# ESP32-S3_Devkit_Replica.net
KiCad netlist of a schematic drawn in Altium Designer
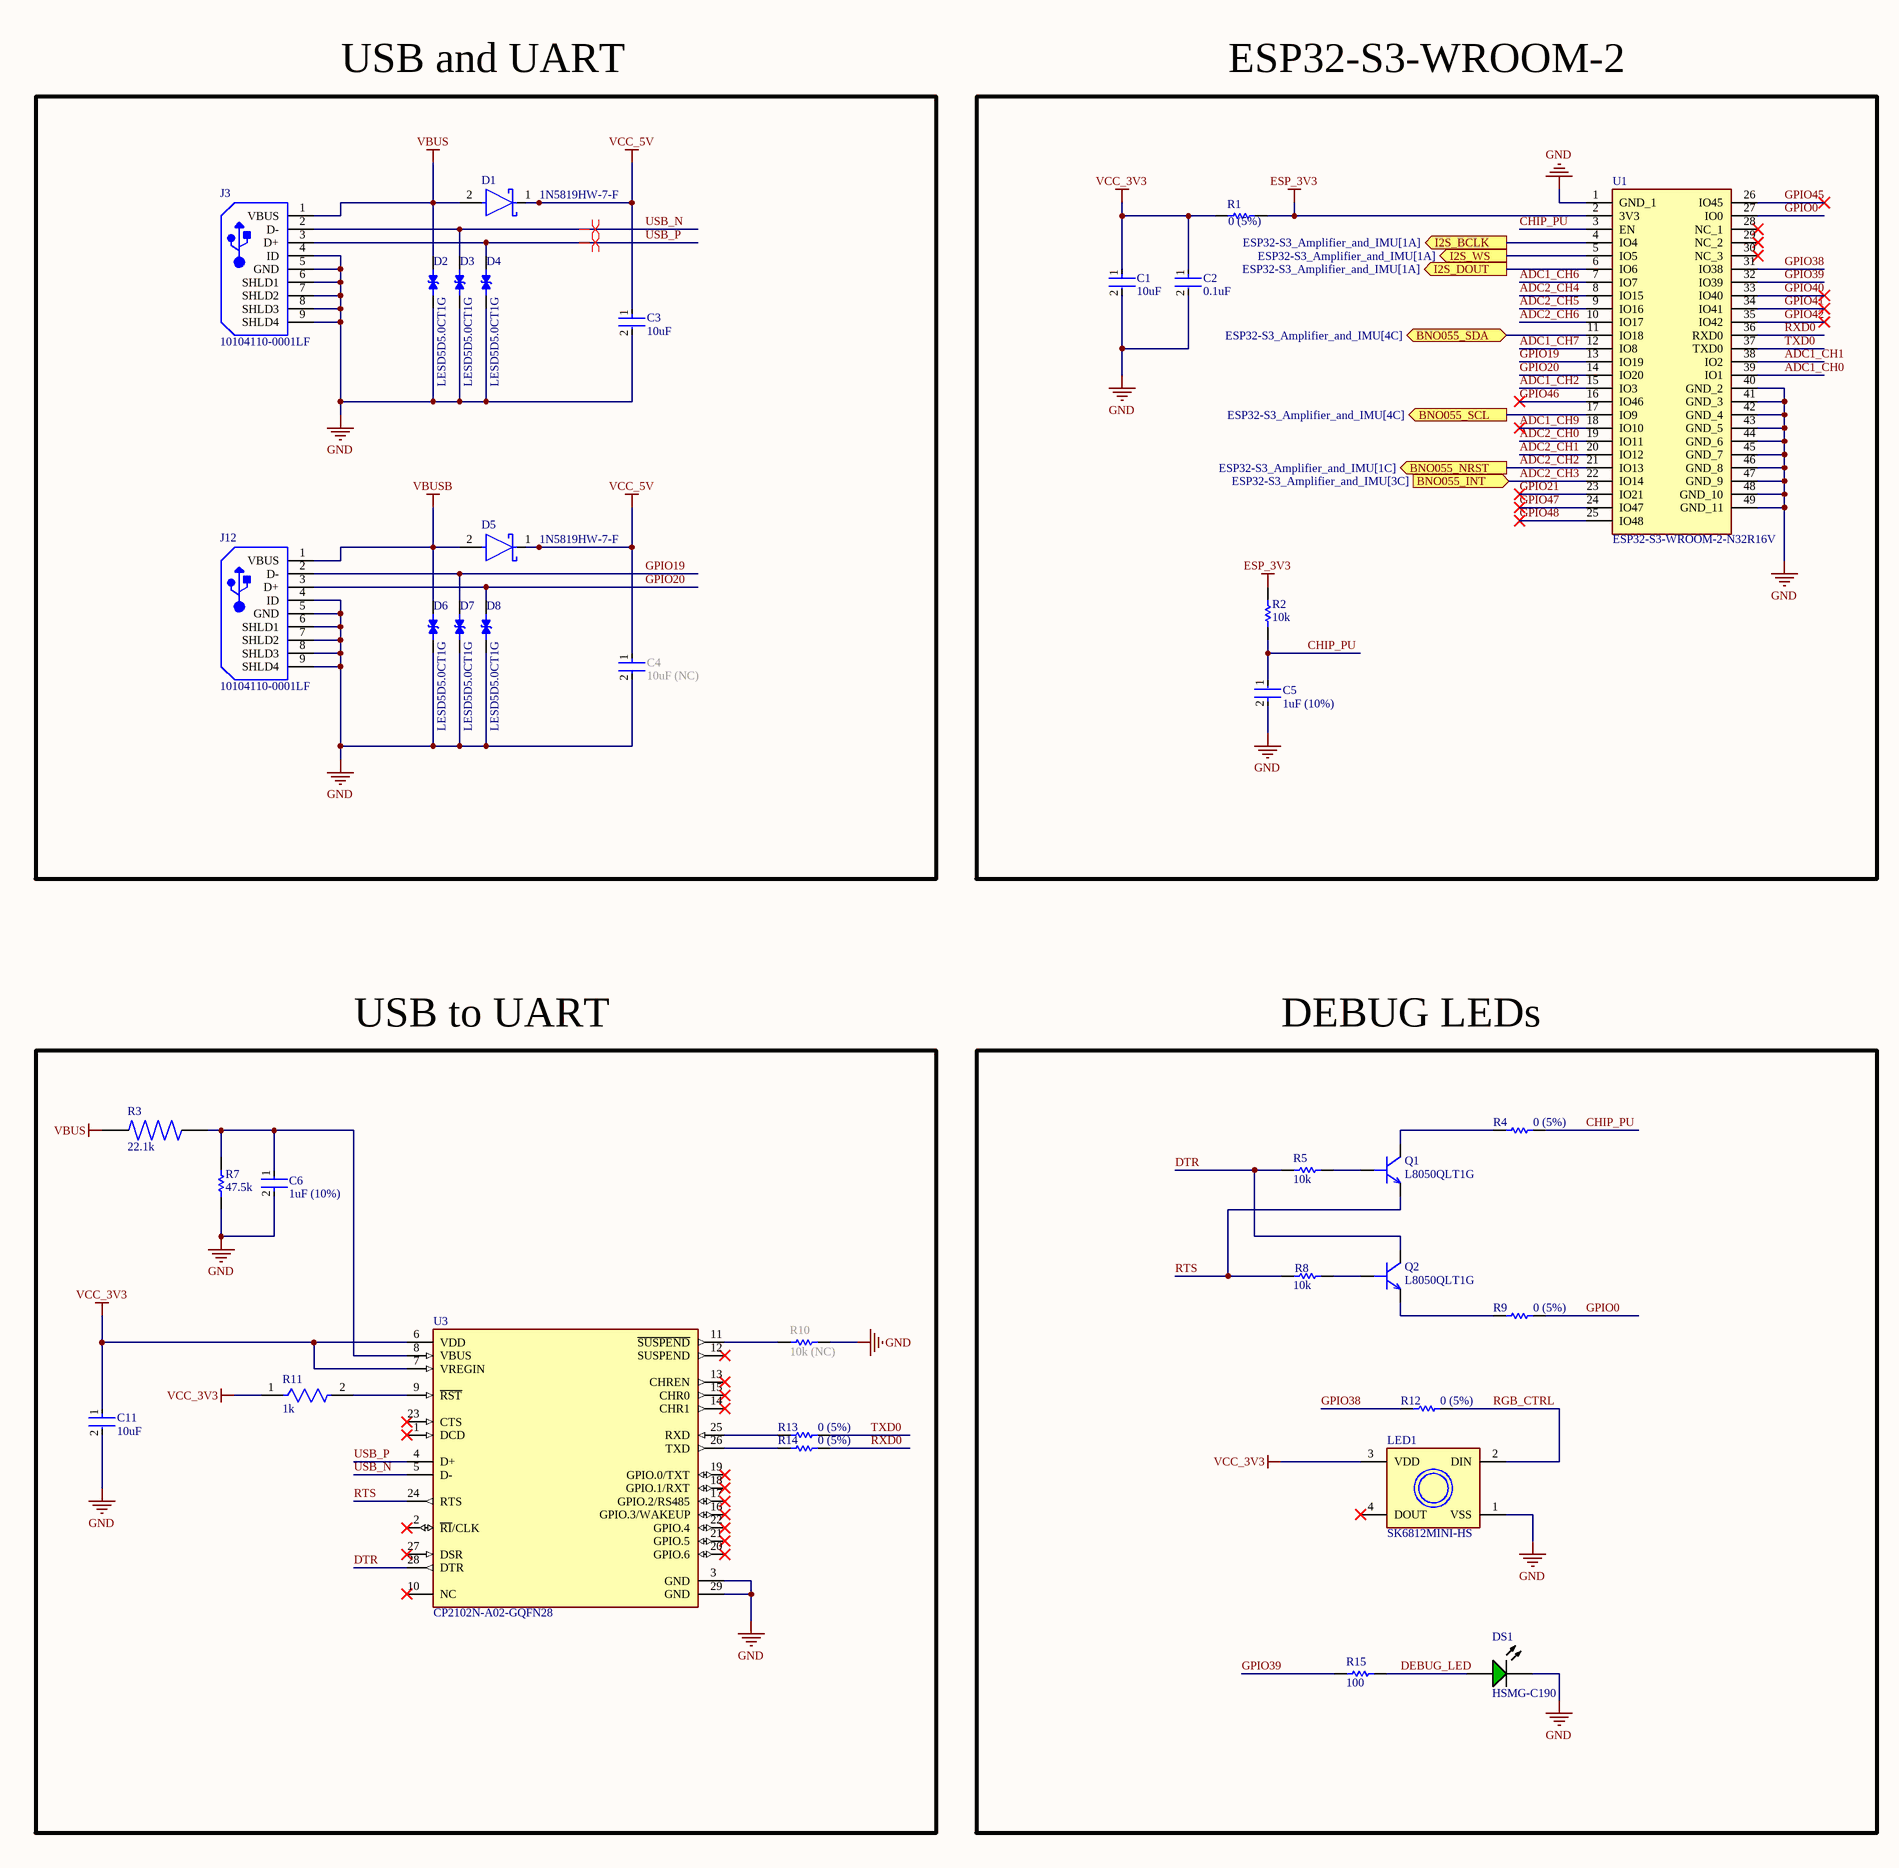
[diagram p0: ESP32-S3_Devkit_Replica.SchDoc, left]
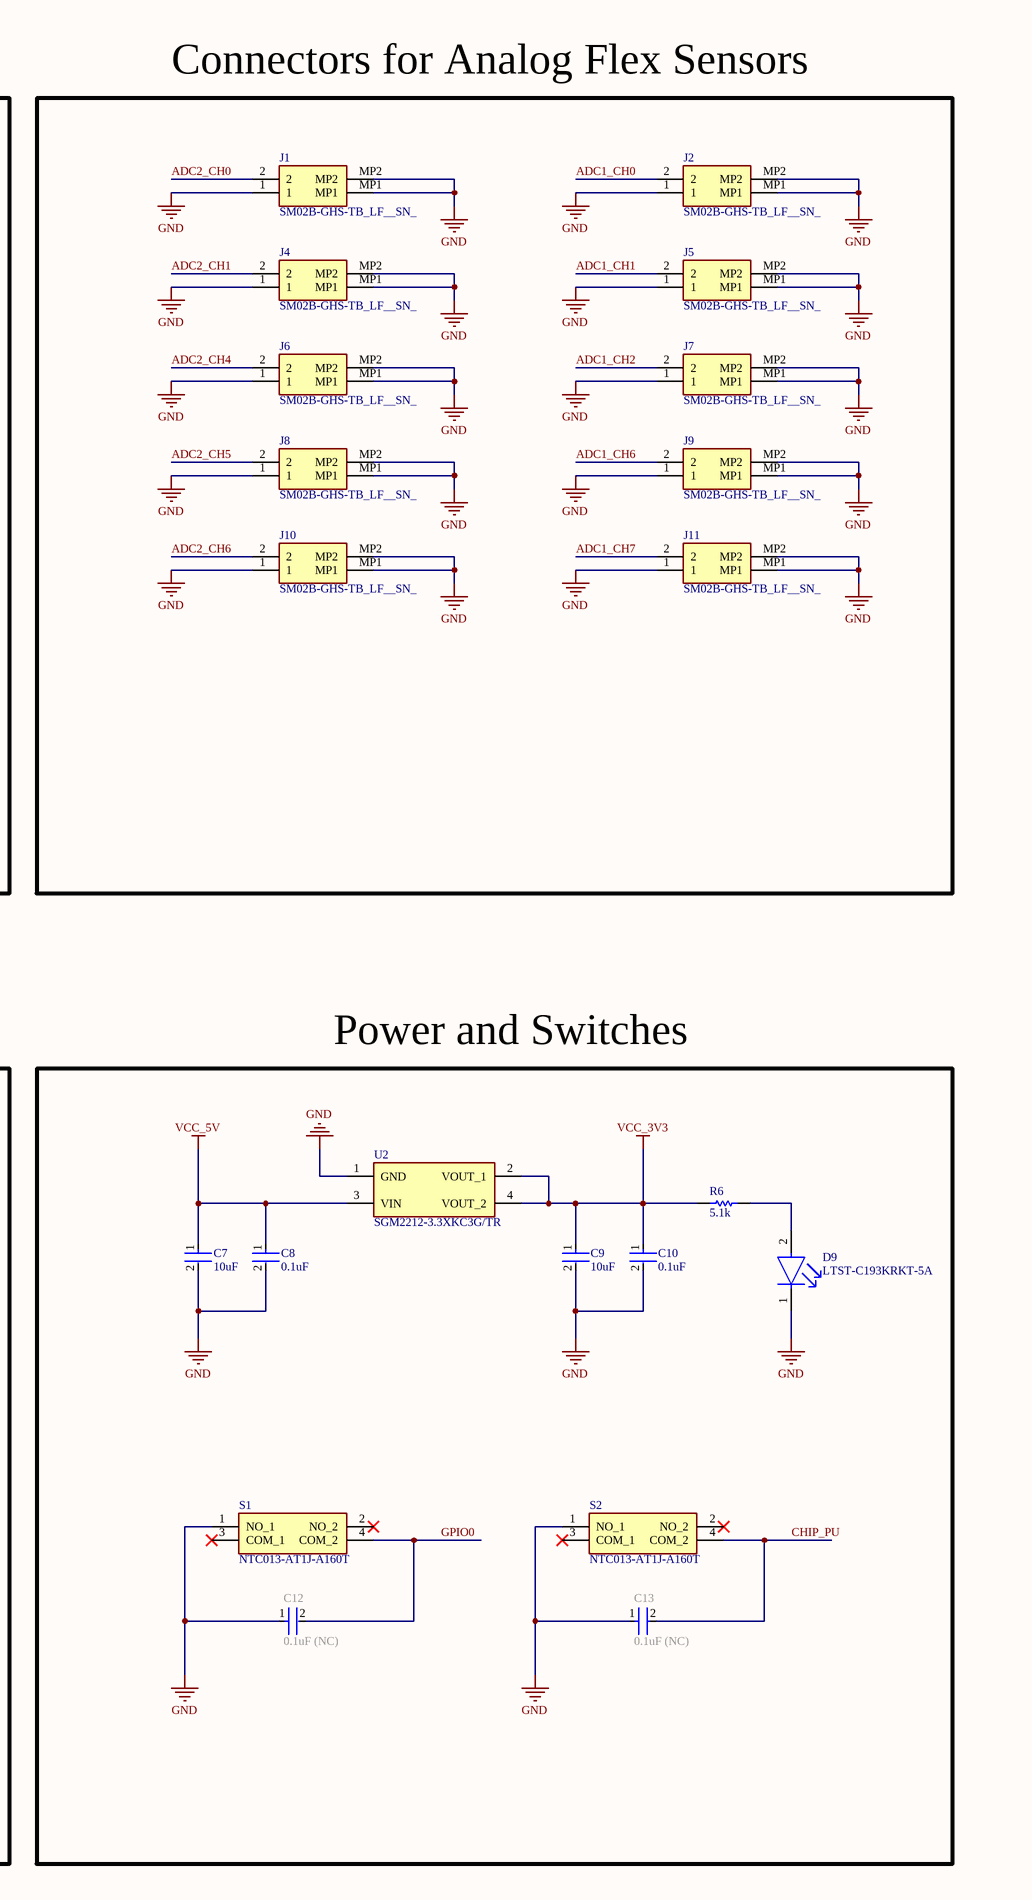
[diagram p1: ESP32-S3_Devkit_Replica.SchDoc, right]

(export (version "E")
  (design (tool "Eeschema 10.0.6"))
  (components
    (comp (ref "C1")
      (value "GRM21BC8YA106KE11L")
      (footprint "FP-GRM21B-0_2-e0_2_0_7-IPC_B")
      (description "Chip Multilayer Ceramic Capacitors for General Purpose, 0805, 10uF, X6S, 22%, 10%, 35V")
      (fields (field (name "CAPACITANCE") "10uF") (field (name "TOLERANCE") "10%"))
      (libsource (lib "Altium Content Vault") (part "b4654b650e69147ec39a6b967a45e02"))
    )
    (comp (ref "C2")
      (value "C1005X7R1H104K050BB")
      (footprint "FP-C1005-050-0_05-IPC_C")
      (description "Multilayer Ceramic Capacitors 100nF ±10% 50V X7R SMD 0402")
      (fields
        (field (name "VOLTAGE") "50V")
        (field (name "CAPACITANCE") "0.1uF")
        (field (name "TOLERANCE") "10%")
      )
      (libsource (lib "Altium Content Vault") (part "b4654b650e69147ec39a6b967a45e02"))
    )
    (comp (ref "C3")
      (value "GRM21BC8YA106KE11L")
      (footprint "FP-GRM21B-0_2-e0_2_0_7-IPC_B")
      (description "Chip Multilayer Ceramic Capacitors for General Purpose, 0805, 10uF, X6S, 22%, 10%, 35V")
      (fields (field (name "CAPACITANCE") "10uF") (field (name "TOLERANCE") "10%"))
      (libsource (lib "Altium Content Vault") (part "b4654b650e69147ec39a6b967a45e02"))
    )
    (comp (ref "C4")
      (value "GRM21BC8YA106KE11L")
      (footprint "FP-GRM21B-0_2-e0_2_0_7-IPC_B")
      (description "Chip Multilayer Ceramic Capacitors for General Purpose, 0805, 10uF, X6S, 22%, 10%, 35V")
      (fields (field (name "CAPACITANCE") "10uF (NC)") (field (name "TOLERANCE") "10%"))
      (libsource (lib "Altium Content Vault") (part "b4654b650e69147ec39a6b967a45e02"))
    )
    (comp (ref "C5")
      (value "C1608X5R1H105K080AB")
      (footprint "FP-C1608-080-0_1-IPC_B")
      (description "Multilayer Ceramic Capacitors 1μF ±10% 50V X5R SMD 0603")
      (fields
        (field (name "VOLTAGE") "50V")
        (field (name "CAPACITANCE") "1uF (10%)")
        (field (name "TOLERANCE") "10%")
      )
      (libsource (lib "Altium Content Vault") (part "236180d848d6139a670b325ea6854c9"))
    )
    (comp (ref "C6")
      (value "C1608X5R1H105K080AB")
      (footprint "FP-C1608-080-0_1-IPC_B")
      (description "Multilayer Ceramic Capacitors 1μF ±10% 50V X5R SMD 0603")
      (fields
        (field (name "VOLTAGE") "50V")
        (field (name "CAPACITANCE") "1uF (10%)")
        (field (name "TOLERANCE") "10%")
      )
      (libsource (lib "Altium Content Vault") (part "236180d848d6139a670b325ea6854c9"))
    )
    (comp (ref "C7")
      (value "GRM21BC8YA106KE11L")
      (footprint "FP-GRM21B-0_2-e0_2_0_7-IPC_B")
      (description "Chip Multilayer Ceramic Capacitors for General Purpose, 0805, 10uF, X6S, 22%, 10%, 35V")
      (fields (field (name "CAPACITANCE") "10uF") (field (name "TOLERANCE") "10%"))
      (libsource (lib "Altium Content Vault") (part "b4654b650e69147ec39a6b967a45e02"))
    )
    (comp (ref "C8")
      (value "C1005X7R1H104K050BB")
      (footprint "FP-C1005-050-0_05-IPC_C")
      (description "Multilayer Ceramic Capacitors 100nF ±10% 50V X7R SMD 0402")
      (fields
        (field (name "VOLTAGE") "50V")
        (field (name "CAPACITANCE") "0.1uF")
        (field (name "TOLERANCE") "10%")
      )
      (libsource (lib "Altium Content Vault") (part "b4654b650e69147ec39a6b967a45e02"))
    )
    (comp (ref "C9")
      (value "GRM21BC8YA106KE11L")
      (footprint "FP-GRM21B-0_2-e0_2_0_7-IPC_B")
      (description "Chip Multilayer Ceramic Capacitors for General Purpose, 0805, 10uF, X6S, 22%, 10%, 35V")
      (fields (field (name "CAPACITANCE") "10uF") (field (name "TOLERANCE") "10%"))
      (libsource (lib "Altium Content Vault") (part "b4654b650e69147ec39a6b967a45e02"))
    )
    (comp (ref "C10")
      (value "C1005X7R1H104K050BB")
      (footprint "FP-C1005-050-0_05-IPC_C")
      (description "Multilayer Ceramic Capacitors 100nF ±10% 50V X7R SMD 0402")
      (fields
        (field (name "VOLTAGE") "50V")
        (field (name "CAPACITANCE") "0.1uF")
        (field (name "TOLERANCE") "10%")
      )
      (libsource (lib "Altium Content Vault") (part "b4654b650e69147ec39a6b967a45e02"))
    )
    (comp (ref "C11")
      (value "GRM21BC8YA106KE11L")
      (footprint "FP-GRM21B-0_2-e0_2_0_7-IPC_B")
      (description "Chip Multilayer Ceramic Capacitors for General Purpose, 0805, 10uF, X6S, 22%, 10%, 35V")
      (fields (field (name "CAPACITANCE") "10uF") (field (name "TOLERANCE") "10%"))
      (libsource (lib "Altium Content Vault") (part "b4654b650e69147ec39a6b967a45e02"))
    )
    (comp (ref "C12")
      (value "C1005X7R1H104K050BB")
      (footprint "FP-C1005-050-0_05-IPC_C")
      (description "Multilayer Ceramic Capacitors 100nF ±10% 50V X7R SMD 0402")
      (fields
        (field (name "VOLTAGE") "50V")
        (field (name "CAPACITANCE") "0.1uF (NC)")
        (field (name "TOLERANCE") "10%")
      )
      (libsource (lib "Altium Content Vault") (part "b4654b650e69147ec39a6b967a45e02"))
    )
    (comp (ref "C13")
      (value "C1005X7R1H104K050BB")
      (footprint "FP-C1005-050-0_05-IPC_C")
      (description "Multilayer Ceramic Capacitors 100nF ±10% 50V X7R SMD 0402")
      (fields
        (field (name "VOLTAGE") "50V")
        (field (name "CAPACITANCE") "0.1uF (NC)")
        (field (name "TOLERANCE") "10%")
      )
      (libsource (lib "Altium Content Vault") (part "b4654b650e69147ec39a6b967a45e02"))
    )
    (comp (ref "D1")
      (value "1N5819HW-7-F")
      (footprint "FP-SOD123-IPC_A")
      (description "DIODE SCHOTTKY 40V 1A SOD123")
      (libsource (lib "Altium Content Vault") (part "1d6ec82d83fb6aee721767c19dac4b9"))
    )
    (comp (ref "D2")
      (value "LESD5D5.0CT1G")
      (footprint "TVS_LESD5D5.0CT1G")
      (description "Transient Voltage Suppressors for ESD Protection")
      (fields (field (name "MF") "Leshan Radio Co."))
      (libsource (lib "GesturaGloveComponents") (part "LESD5D5.0CT1G"))
    )
    (comp (ref "D3")
      (value "LESD5D5.0CT1G")
      (footprint "TVS_LESD5D5.0CT1G")
      (description "Transient Voltage Suppressors for ESD Protection")
      (fields (field (name "MF") "Leshan Radio Co."))
      (libsource (lib "GesturaGloveComponents") (part "LESD5D5.0CT1G"))
    )
    (comp (ref "D4")
      (value "LESD5D5.0CT1G")
      (footprint "TVS_LESD5D5.0CT1G")
      (description "Transient Voltage Suppressors for ESD Protection")
      (fields (field (name "MF") "Leshan Radio Co."))
      (libsource (lib "GesturaGloveComponents") (part "LESD5D5.0CT1G"))
    )
    (comp (ref "D5")
      (value "1N5819HW-7-F")
      (footprint "FP-SOD123-IPC_A")
      (description "DIODE SCHOTTKY 40V 1A SOD123")
      (libsource (lib "Altium Content Vault") (part "1d6ec82d83fb6aee721767c19dac4b9"))
    )
    (comp (ref "D6")
      (value "LESD5D5.0CT1G")
      (footprint "TVS_LESD5D5.0CT1G")
      (description "Transient Voltage Suppressors for ESD Protection")
      (fields (field (name "MF") "Leshan Radio Co."))
      (libsource (lib "GesturaGloveComponents") (part "LESD5D5.0CT1G"))
    )
    (comp (ref "D7")
      (value "LESD5D5.0CT1G")
      (footprint "TVS_LESD5D5.0CT1G")
      (description "Transient Voltage Suppressors for ESD Protection")
      (fields (field (name "MF") "Leshan Radio Co."))
      (libsource (lib "GesturaGloveComponents") (part "LESD5D5.0CT1G"))
    )
    (comp (ref "D8")
      (value "LESD5D5.0CT1G")
      (footprint "TVS_LESD5D5.0CT1G")
      (description "Transient Voltage Suppressors for ESD Protection")
      (fields (field (name "MF") "Leshan Radio Co."))
      (libsource (lib "GesturaGloveComponents") (part "LESD5D5.0CT1G"))
    )
    (comp (ref "D9")
      (value "LTST-C193KRKT-5A")
      (footprint "FP-LTST-C193KRKT-5A-MFG")
      (description "LED RED CLEAR CHIP SMD")
      (libsource (lib "Altium Content Vault") (part "8706943c75ba83719d021d2fdc84c58"))
    )
    (comp (ref "DS1")
      (value "HSMG-C190")
      (footprint "AVAG-HSMX-C190_V")
      (description "Chip LED, Green, 2.2 V, -40 to 85 degC, 2-Pin SMD, RoHS, Tape and Reel")
      (libsource (lib "Altium Content Vault") (part "LED-GREEN-AK-2"))
    )
    (comp (ref "J1")
      (value "SM02B-GHS-TB_LF__SN_")
      (footprint "GesturaGloveComponents:SM02BGHSTBLFSN")
      (description "Connector")
      (fields
        (field (name "MANUFACTURER_PART_NUMBER") "SM02B-GHS-TB(LF)(SN);-")
        (field (name "MOUSER PART NUMBER") "306-SM02BGHSTBLFSN")
      )
      (libsource (lib "GesturaGloveComponents") (part "SM02B-GHS-TB_LF__SN_"))
    )
    (comp (ref "J2")
      (value "SM02B-GHS-TB_LF__SN_")
      (footprint "GesturaGloveComponents:SM02BGHSTBLFSN")
      (description "Connector")
      (fields
        (field (name "MANUFACTURER_PART_NUMBER") "SM02B-GHS-TB(LF)(SN);-")
        (field (name "MOUSER PART NUMBER") "306-SM02BGHSTBLFSN")
      )
      (libsource (lib "GesturaGloveComponents") (part "SM02B-GHS-TB_LF__SN_"))
    )
    (comp (ref "J3")
      (value "10104110-0001LF")
      (footprint "FCI-10104110-0001LF_V")
      (description "Micro USB, Receptacle, -55 to 85 degC, 5-Pin SMD, RoHS, Tape and Reel")
      (fields (field (name "MANUFACTURER") "FCI Electronics"))
      (libsource (lib "Altium Content Vault") (part "USB-5-4SHLD"))
    )
    (comp (ref "J4")
      (value "SM02B-GHS-TB_LF__SN_")
      (footprint "GesturaGloveComponents:SM02BGHSTBLFSN")
      (description "Connector")
      (fields
        (field (name "MANUFACTURER_PART_NUMBER") "SM02B-GHS-TB(LF)(SN);-")
        (field (name "MOUSER PART NUMBER") "306-SM02BGHSTBLFSN")
      )
      (libsource (lib "GesturaGloveComponents") (part "SM02B-GHS-TB_LF__SN_"))
    )
    (comp (ref "J5")
      (value "SM02B-GHS-TB_LF__SN_")
      (footprint "GesturaGloveComponents:SM02BGHSTBLFSN")
      (description "Connector")
      (fields
        (field (name "MANUFACTURER_PART_NUMBER") "SM02B-GHS-TB(LF)(SN);-")
        (field (name "MOUSER PART NUMBER") "306-SM02BGHSTBLFSN")
      )
      (libsource (lib "GesturaGloveComponents") (part "SM02B-GHS-TB_LF__SN_"))
    )
    (comp (ref "J6")
      (value "SM02B-GHS-TB_LF__SN_")
      (footprint "GesturaGloveComponents:SM02BGHSTBLFSN")
      (description "Connector")
      (fields
        (field (name "MANUFACTURER_PART_NUMBER") "SM02B-GHS-TB(LF)(SN);-")
        (field (name "MOUSER PART NUMBER") "306-SM02BGHSTBLFSN")
      )
      (libsource (lib "GesturaGloveComponents") (part "SM02B-GHS-TB_LF__SN_"))
    )
    (comp (ref "J7")
      (value "SM02B-GHS-TB_LF__SN_")
      (footprint "GesturaGloveComponents:SM02BGHSTBLFSN")
      (description "Connector")
      (fields
        (field (name "MANUFACTURER_PART_NUMBER") "SM02B-GHS-TB(LF)(SN);-")
        (field (name "MOUSER PART NUMBER") "306-SM02BGHSTBLFSN")
      )
      (libsource (lib "GesturaGloveComponents") (part "SM02B-GHS-TB_LF__SN_"))
    )
    (comp (ref "J8")
      (value "SM02B-GHS-TB_LF__SN_")
      (footprint "GesturaGloveComponents:SM02BGHSTBLFSN")
      (description "Connector")
      (fields
        (field (name "MANUFACTURER_PART_NUMBER") "SM02B-GHS-TB(LF)(SN);-")
        (field (name "MOUSER PART NUMBER") "306-SM02BGHSTBLFSN")
      )
      (libsource (lib "GesturaGloveComponents") (part "SM02B-GHS-TB_LF__SN_"))
    )
    (comp (ref "J9")
      (value "SM02B-GHS-TB_LF__SN_")
      (footprint "GesturaGloveComponents:SM02BGHSTBLFSN")
      (description "Connector")
      (fields
        (field (name "MANUFACTURER_PART_NUMBER") "SM02B-GHS-TB(LF)(SN);-")
        (field (name "MOUSER PART NUMBER") "306-SM02BGHSTBLFSN")
      )
      (libsource (lib "GesturaGloveComponents") (part "SM02B-GHS-TB_LF__SN_"))
    )
    (comp (ref "J10")
      (value "SM02B-GHS-TB_LF__SN_")
      (footprint "GesturaGloveComponents:SM02BGHSTBLFSN")
      (description "Connector")
      (fields
        (field (name "MANUFACTURER_PART_NUMBER") "SM02B-GHS-TB(LF)(SN);-")
        (field (name "MOUSER PART NUMBER") "306-SM02BGHSTBLFSN")
      )
      (libsource (lib "GesturaGloveComponents") (part "SM02B-GHS-TB_LF__SN_"))
    )
    (comp (ref "J11")
      (value "SM02B-GHS-TB_LF__SN_")
      (footprint "GesturaGloveComponents:SM02BGHSTBLFSN")
      (description "Connector")
      (fields
        (field (name "MANUFACTURER_PART_NUMBER") "SM02B-GHS-TB(LF)(SN);-")
        (field (name "MOUSER PART NUMBER") "306-SM02BGHSTBLFSN")
      )
      (libsource (lib "GesturaGloveComponents") (part "SM02B-GHS-TB_LF__SN_"))
    )
    (comp (ref "J12")
      (value "10104110-0001LF")
      (footprint "FCI-10104110-0001LF_V")
      (description "Micro USB, Receptacle, -55 to 85 degC, 5-Pin SMD, RoHS, Tape and Reel")
      (fields (field (name "MANUFACTURER") "FCI Electronics"))
      (libsource (lib "Altium Content Vault") (part "USB-5-4SHLD"))
    )
    (comp (ref "LED1")
      (value "SK6812MINI-HS")
      (footprint "GesturaGloveComponents:SK6812MINI-HS")
      (description "LED")
      (fields (field (name "MANUFACTURER_PART_NUMBER") "ILPH-K501-RGBW-SK6812-05-01"))
      (libsource (lib "GesturaGloveComponents") (part "SK6812MINI-HS"))
    )
    (comp (ref "Q1")
      (value "L8050QLT1G")
      (footprint "L8050QLT1G")
      (description "25V 225mW 800mA NPN SOT-23(SOT-23-3) Bipolar Transistors - BJT ROHS")
      (libsource (lib "GesturaGloveComponents") (part "L8050QLT1G"))
    )
    (comp (ref "Q2")
      (value "L8050QLT1G")
      (footprint "L8050QLT1G")
      (description "25V 225mW 800mA NPN SOT-23(SOT-23-3) Bipolar Transistors - BJT ROHS")
      (libsource (lib "GesturaGloveComponents") (part "L8050QLT1G"))
    )
    (comp (ref "R1")
      (value "ERJ2GE0R00X")
      (footprint "RESC1005X40X25LL05T05")
      (description "Chip Resistor, 0 Ohm, 0.1 W, -55 to 155 degC, 0402 (1005 Metric), RoHS, Tape and Reel")
      (fields
        (field (name "MANUFACTURER") "Panasonic")
        (field (name "RESISTANCE") "0 (5%)")
        (field (name "TOLERANCE") "5%")
      )
      (libsource (lib "Altium Content Vault") (part "RES-2"))
    )
    (comp (ref "R2")
      (value "CRCW040210K0FKEDHP")
      (footprint "RESC1005X40X25ML05T10")
      (description "1")
      (fields (field (name "MANUFACTURER") "Vishay Dale") (field (name "RESISTANCE") "10k"))
      (libsource (lib "Altium Content Vault") (part "RES"))
    )
    (comp (ref "R3")
      (value "22.1k")
      (footprint "GesturaGloveComponents:RES_ERA2AEB2212X")
      (description "Res Thin Film 0402 22.1K Ohm 0.1% 1/16W ±25ppm/°C Molded SMD Punched Paper T/R")
      (fields (field (name "MP") "ERA2AEB2212X"))
      (libsource (lib "GesturaGloveComponents") (part "ERA2AEB2212X"))
    )
    (comp (ref "R4")
      (value "ERJ2GE0R00X")
      (footprint "RESC1005X40X25LL05T05")
      (description "Chip Resistor, 0 Ohm, 0.1 W, -55 to 155 degC, 0402 (1005 Metric), RoHS, Tape and Reel")
      (fields
        (field (name "MANUFACTURER") "Panasonic")
        (field (name "RESISTANCE") "0 (5%)")
        (field (name "TOLERANCE") "5%")
      )
      (libsource (lib "Altium Content Vault") (part "RES-2"))
    )
    (comp (ref "R5")
      (value "CRCW040210K0FKEDHP")
      (footprint "RESC1005X40X25ML05T10")
      (description "1")
      (fields (field (name "MANUFACTURER") "Vishay Dale") (field (name "RESISTANCE") "10k"))
      (libsource (lib "Altium Content Vault") (part "RES"))
    )
    (comp (ref "R6")
      (value "RC0402FR-075K1L")
      (footprint "RESC1005X40X25NL05T10")
      (fields (field (name "MANUFACTURER") "Yageo / Phycomp") (field (name "RESISTANCE") "5.1k"))
      (libsource (lib "Altium Content Vault") (part "RES"))
    )
    (comp (ref "R7")
      (value "CRCW040247K5FKTD")
      (footprint "RESC1005X40X25LL05T05")
      (fields (field (name "MANUFACTURER") "Vishay Dale") (field (name "RESISTANCE") "47.5k"))
      (libsource (lib "Altium Content Vault") (part "RES"))
    )
    (comp (ref "R8")
      (value "CRCW040210K0FKEDHP")
      (footprint "RESC1005X40X25ML05T10")
      (description "1")
      (fields (field (name "MANUFACTURER") "Vishay Dale") (field (name "RESISTANCE") "10k"))
      (libsource (lib "Altium Content Vault") (part "RES"))
    )
    (comp (ref "R9")
      (value "ERJ2GE0R00X")
      (footprint "RESC1005X40X25LL05T05")
      (description "Chip Resistor, 0 Ohm, 0.1 W, -55 to 155 degC, 0402 (1005 Metric), RoHS, Tape and Reel")
      (fields
        (field (name "MANUFACTURER") "Panasonic")
        (field (name "RESISTANCE") "0 (5%)")
        (field (name "TOLERANCE") "5%")
      )
      (libsource (lib "Altium Content Vault") (part "RES-2"))
    )
    (comp (ref "R10")
      (value "CRCW040210K0FKEDHP")
      (footprint "RESC1005X40X25ML05T10")
      (description "1")
      (fields (field (name "MANUFACTURER") "Vishay Dale") (field (name "RESISTANCE") "10k (NC)"))
      (libsource (lib "Altium Content Vault") (part "RES"))
    )
    (comp (ref "R11")
      (value "TFCR0402-16W-C-1001BT-1K")
      (footprint "FP-TFCR0402-IPC_A")
      (description "RES Thin Film,  1kΩ, 0.1%, 0.063W, 50ppm/°C, 0402")
      (fields (field (name "RESISTANCE") "1k"))
      (libsource (lib "Altium Content Vault") (part "1029c3af85768c4190bb7ad29bc67b5"))
    )
    (comp (ref "R12")
      (value "ERJ2GE0R00X")
      (footprint "RESC1005X40X25LL05T05")
      (description "Chip Resistor, 0 Ohm, 0.1 W, -55 to 155 degC, 0402 (1005 Metric), RoHS, Tape and Reel")
      (fields
        (field (name "MANUFACTURER") "Panasonic")
        (field (name "RESISTANCE") "0 (5%)")
        (field (name "TOLERANCE") "5%")
      )
      (libsource (lib "Altium Content Vault") (part "RES-2"))
    )
    (comp (ref "R13")
      (value "ERJ2GE0R00X")
      (footprint "RESC1005X40X25LL05T05")
      (description "Chip Resistor, 0 Ohm, 0.1 W, -55 to 155 degC, 0402 (1005 Metric), RoHS, Tape and Reel")
      (fields
        (field (name "MANUFACTURER") "Panasonic")
        (field (name "RESISTANCE") "0 (5%)")
        (field (name "TOLERANCE") "5%")
      )
      (libsource (lib "Altium Content Vault") (part "RES-2"))
    )
    (comp (ref "R14")
      (value "ERJ2GE0R00X")
      (footprint "RESC1005X40X25LL05T05")
      (description "Chip Resistor, 0 Ohm, 0.1 W, -55 to 155 degC, 0402 (1005 Metric), RoHS, Tape and Reel")
      (fields
        (field (name "MANUFACTURER") "Panasonic")
        (field (name "RESISTANCE") "0 (5%)")
        (field (name "TOLERANCE") "5%")
      )
      (libsource (lib "Altium Content Vault") (part "RES-2"))
    )
    (comp (ref "R15")
      (value "ERJ-2RKF1000X")
      (footprint "RESC1005X40X25LL05T05")
      (description "Chip Resistor, 100 Ohm, +/- 1%, 100 mW, -55 to 155 degC, 0402 (1005 Metric), RoHS, Tape and Reel")
      (fields
        (field (name "MANUFACTURER") "Basic Passives")
        (field (name "TOLERANCE") "1%")
        (field (name "RESISTANCE") "100")
      )
      (libsource (lib "Altium Content Vault") (part "RES-2"))
    )
    (comp (ref "S1")
      (value "NTC013-AT1J-A160T")
      (footprint "GesturaGloveComponents:NTC013AT1JA160T")
      (description "4-pin Switch")
      (libsource (lib "GesturaGloveComponents") (part "NTC013-AT1J-A160T"))
    )
    (comp (ref "S2")
      (value "NTC013-AT1J-A160T")
      (footprint "GesturaGloveComponents:NTC013AT1JA160T")
      (description "4-pin Switch")
      (libsource (lib "GesturaGloveComponents") (part "NTC013-AT1J-A160T"))
    )
    (comp (ref "U1")
      (value "ESP32-S3-WROOM-2-N32R16V")
      (footprint "ESP32S3WROOM2N32R16V")
      (description "Bluetooth, WiFi 802.11b/g/n, Bluetooth v5.0 Transceiver Module 2.4GHz PCB Trace Surface Mount")
      (fields (field (name "MOUSER PART NUMBER") "356-SP32S3WM2N32R16V"))
      (libsource (lib "GesturaGloveComponents") (part "ESP32-S3-WROOM-2-N32R16V"))
    )
    (comp (ref "U2")
      (value "SGM2212-3.3XKC3G/TR")
      (footprint "GesturaGloveComponents:SOT230P700X180-4N")
      (description "80dB@(120Hz) 80μA fixed 800mA 1 3.3V 2.7V 3.3V 20V 450mV@(800mA) 0.4% (MAX) SOT-223-3")
      (libsource (lib "GesturaGloveComponents") (part "SGM2212-3.3XKC3G_TR"))
    )
    (comp (ref "U3")
      (value "CP2102N-A02-GQFN28")
      (footprint "FP-CP2102N-A02-GQFN28-MFG")
      (description "IC USB TO UART BRIDGE QFN28")
      (libsource (lib "Altium Content Vault") (part "f8fb43f618a03b32512863a7a8093b6"))
    )
  )
  (nets
    (net (code "1") (name "/ADC1_CH0") (class "Default")
      (node (ref "J2") (pin "2") (pinfunction "2_2") (pintype "passive"))
      (node (ref "U1") (pin "39") (pinfunction "IO1_39") (pintype "passive"))
    )
    (net (code "2") (name "/ADC1_CH1") (class "Default")
      (node (ref "J5") (pin "2") (pinfunction "2_2") (pintype "passive"))
      (node (ref "U1") (pin "38") (pinfunction "IO2_38") (pintype "passive"))
    )
    (net (code "3") (name "/ADC1_CH2") (class "Default")
      (node (ref "J7") (pin "2") (pinfunction "2_2") (pintype "passive"))
      (node (ref "U1") (pin "15") (pinfunction "IO3_15") (pintype "passive"))
    )
    (net (code "4") (name "/ADC1_CH6") (class "Default")
      (node (ref "J9") (pin "2") (pinfunction "2_2") (pintype "passive"))
      (node (ref "U1") (pin "7") (pinfunction "IO7_7") (pintype "passive"))
    )
    (net (code "5") (name "/ADC1_CH7") (class "Default")
      (node (ref "J11") (pin "2") (pinfunction "2_2") (pintype "passive"))
      (node (ref "U1") (pin "12") (pinfunction "IO8_12") (pintype "passive"))
    )
    (net (code "6") (name "/ADC1_CH9") (class "Default")
      (node (ref "U1") (pin "18") (pinfunction "IO10_18") (pintype "passive+no_connect"))
    )
    (net (code "7") (name "/ADC2_CH0") (class "Default")
      (node (ref "J1") (pin "2") (pinfunction "2_2") (pintype "passive"))
      (node (ref "U1") (pin "19") (pinfunction "IO11_19") (pintype "passive"))
    )
    (net (code "8") (name "/ADC2_CH1") (class "Default")
      (node (ref "J4") (pin "2") (pinfunction "2_2") (pintype "passive"))
      (node (ref "U1") (pin "20") (pinfunction "IO12_20") (pintype "passive"))
    )
    (net (code "9") (name "/ADC2_CH2") (class "Default")
      (node (ref "U1") (pin "21") (pinfunction "IO13_21") (pintype "passive"))
    )
    (net (code "10") (name "/ADC2_CH3") (class "Default")
      (node (ref "U1") (pin "22") (pinfunction "IO14_22") (pintype "passive"))
    )
    (net (code "11") (name "/ADC2_CH4") (class "Default")
      (node (ref "J6") (pin "2") (pinfunction "2_2") (pintype "passive"))
      (node (ref "U1") (pin "8") (pinfunction "IO15_8") (pintype "passive"))
    )
    (net (code "12") (name "/ADC2_CH5") (class "Default")
      (node (ref "J8") (pin "2") (pinfunction "2_2") (pintype "passive"))
      (node (ref "U1") (pin "9") (pinfunction "IO16_9") (pintype "passive"))
    )
    (net (code "13") (name "/ADC2_CH6") (class "Default")
      (node (ref "J10") (pin "2") (pinfunction "2_2") (pintype "passive"))
      (node (ref "U1") (pin "10") (pinfunction "IO17_10") (pintype "passive"))
    )
    (net (code "14") (name "/BNO055_SCL") (class "Default")
      (node (ref "U1") (pin "17") (pinfunction "IO9_17") (pintype "passive"))
    )
    (net (code "15") (name "/BNO055_SDA") (class "Default")
      (node (ref "U1") (pin "11") (pinfunction "IO18_11") (pintype "passive"))
    )
    (net (code "16") (name "/CHIP_PU") (class "Default")
      (node (ref "C13") (pin "2") (pinfunction "2_2") (pintype "passive"))
      (node (ref "C5") (pin "1") (pinfunction "1_1") (pintype "passive"))
      (node (ref "R2") (pin "1") (pinfunction "1_1") (pintype "passive"))
      (node (ref "R4") (pin "2") (pinfunction "2_2") (pintype "passive"))
      (node (ref "S2") (pin "4") (pinfunction "COM_2_4") (pintype "passive"))
      (node (ref "U1") (pin "3") (pinfunction "EN_3") (pintype "passive"))
    )
    (net (code "17") (name "/DEBUG_LED") (class "Default")
      (node (ref "DS1") (pin "1") (pinfunction "A_1") (pintype "passive"))
      (node (ref "R15") (pin "1") (pinfunction "1_1") (pintype "passive"))
    )
    (net (code "18") (name "/DTR") (class "Default")
      (node (ref "Q2") (pin "1") (pinfunction "C_1") (pintype "passive"))
      (node (ref "R5") (pin "2") (pinfunction "2_2") (pintype "passive"))
      (node (ref "U3") (pin "28") (pinfunction "DTR_28") (pintype "output"))
    )
    (net (code "19") (name "/GPIO0") (class "Default")
      (node (ref "C12") (pin "2") (pinfunction "2_2") (pintype "passive"))
      (node (ref "R9") (pin "2") (pinfunction "2_2") (pintype "passive"))
      (node (ref "S1") (pin "4") (pinfunction "COM_2_4") (pintype "passive"))
      (node (ref "U1") (pin "27") (pinfunction "IO0_27") (pintype "passive"))
    )
    (net (code "20") (name "/GPIO19") (class "Default")
      (node (ref "D7") (pin "1") (pinfunction "1_1") (pintype "passive"))
      (node (ref "J12") (pin "2") (pinfunction "D-_2") (pintype "passive"))
      (node (ref "U1") (pin "13") (pinfunction "IO19_13") (pintype "passive"))
    )
    (net (code "21") (name "/GPIO20") (class "Default")
      (node (ref "D8") (pin "1") (pinfunction "1_1") (pintype "passive"))
      (node (ref "J12") (pin "3") (pinfunction "D+_3") (pintype "passive"))
      (node (ref "U1") (pin "14") (pinfunction "IO20_14") (pintype "passive"))
    )
    (net (code "22") (name "/GPIO21") (class "Default")
      (node (ref "U1") (pin "23") (pinfunction "IO21_23") (pintype "passive+no_connect"))
    )
    (net (code "23") (name "/GPIO38") (class "Default")
      (node (ref "R12") (pin "1") (pinfunction "1_1") (pintype "passive"))
      (node (ref "U1") (pin "31") (pinfunction "IO38_31") (pintype "passive"))
    )
    (net (code "24") (name "/GPIO39") (class "Default")
      (node (ref "R15") (pin "2") (pinfunction "2_2") (pintype "passive"))
      (node (ref "U1") (pin "32") (pinfunction "IO39_32") (pintype "passive"))
    )
    (net (code "25") (name "/GPIO40") (class "Default")
      (node (ref "U1") (pin "33") (pinfunction "IO40_33") (pintype "passive+no_connect"))
    )
    (net (code "26") (name "/GPIO41") (class "Default")
      (node (ref "U1") (pin "34") (pinfunction "IO41_34") (pintype "passive+no_connect"))
    )
    (net (code "27") (name "/GPIO42") (class "Default")
      (node (ref "U1") (pin "35") (pinfunction "IO42_35") (pintype "passive+no_connect"))
    )
    (net (code "28") (name "/GPIO45") (class "Default")
      (node (ref "U1") (pin "26") (pinfunction "IO45_26") (pintype "passive+no_connect"))
    )
    (net (code "29") (name "/GPIO46") (class "Default")
      (node (ref "U1") (pin "16") (pinfunction "IO46_16") (pintype "passive+no_connect"))
    )
    (net (code "30") (name "/GPIO47") (class "Default")
      (node (ref "U1") (pin "24") (pinfunction "IO47_24") (pintype "passive+no_connect"))
    )
    (net (code "31") (name "/GPIO48") (class "Default")
      (node (ref "U1") (pin "25") (pinfunction "IO48_25") (pintype "passive+no_connect"))
    )
    (net (code "32") (name "/I2S_BCLK") (class "Default")
      (node (ref "U1") (pin "4") (pinfunction "IO4_4") (pintype "passive"))
    )
    (net (code "33") (name "/I2S_DOUT") (class "Default")
      (node (ref "U1") (pin "6") (pinfunction "IO6_6") (pintype "passive"))
    )
    (net (code "34") (name "/I2S_WS") (class "Default")
      (node (ref "U1") (pin "5") (pinfunction "IO5_5") (pintype "passive"))
    )
    (net (code "35") (name "/RGB_CTRL") (class "Default")
      (node (ref "LED1") (pin "2") (pinfunction "DIN_2") (pintype "passive"))
      (node (ref "R12") (pin "2") (pinfunction "2_2") (pintype "passive"))
    )
    (net (code "36") (name "/RTS") (class "Default")
      (node (ref "Q1") (pin "2") (pinfunction "E_2") (pintype "passive"))
      (node (ref "R8") (pin "2") (pinfunction "2_2") (pintype "passive"))
      (node (ref "U3") (pin "24") (pinfunction "RTS_24") (pintype "output"))
    )
    (net (code "37") (name "/RXD0") (class "Default")
      (node (ref "R14") (pin "2") (pinfunction "2_2") (pintype "passive"))
      (node (ref "U1") (pin "36") (pinfunction "RXD0_36") (pintype "passive"))
    )
    (net (code "38") (name "/TXD0") (class "Default")
      (node (ref "R13") (pin "2") (pinfunction "2_2") (pintype "passive"))
      (node (ref "U1") (pin "37") (pinfunction "TXD0_37") (pintype "passive"))
    )
    (net (code "39") (name "/USB_N") (class "Default")
      (node (ref "D3") (pin "1") (pinfunction "1_1") (pintype "passive"))
      (node (ref "J3") (pin "2") (pinfunction "D-_2") (pintype "passive"))
      (node (ref "U3") (pin "5") (pinfunction "D-_5") (pintype "passive"))
    )
    (net (code "40") (name "/USB_P") (class "Default")
      (node (ref "D4") (pin "1") (pinfunction "1_1") (pintype "passive"))
      (node (ref "J3") (pin "3") (pinfunction "D+_3") (pintype "passive"))
      (node (ref "U3") (pin "4") (pinfunction "D+_4") (pintype "passive"))
    )
    (net (code "41") (name "ESP_3V3") (class "Default")
      (node (ref "R1") (pin "2") (pinfunction "2_2") (pintype "passive"))
      (node (ref "R2") (pin "2") (pinfunction "2_2") (pintype "passive"))
      (node (ref "U1") (pin "2") (pinfunction "3V3_2") (pintype "passive"))
    )
    (net (code "42") (name "GND") (class "Default")
      (node (ref "C1") (pin "2") (pinfunction "2_2") (pintype "passive"))
      (node (ref "C10") (pin "2") (pinfunction "2_2") (pintype "passive"))
      (node (ref "C11") (pin "2") (pinfunction "2_2") (pintype "passive"))
      (node (ref "C12") (pin "1") (pinfunction "1_1") (pintype "passive"))
      (node (ref "C13") (pin "1") (pinfunction "1_1") (pintype "passive"))
      (node (ref "C2") (pin "2") (pinfunction "2_2") (pintype "passive"))
      (node (ref "C3") (pin "2") (pinfunction "2_2") (pintype "passive"))
      (node (ref "C4") (pin "2") (pinfunction "2_2") (pintype "passive"))
      (node (ref "C5") (pin "2") (pinfunction "2_2") (pintype "passive"))
      (node (ref "C6") (pin "2") (pinfunction "2_2") (pintype "passive"))
      (node (ref "C7") (pin "2") (pinfunction "2_2") (pintype "passive"))
      (node (ref "C8") (pin "2") (pinfunction "2_2") (pintype "passive"))
      (node (ref "C9") (pin "2") (pinfunction "2_2") (pintype "passive"))
      (node (ref "D2") (pin "2") (pinfunction "2_2") (pintype "passive"))
      (node (ref "D3") (pin "2") (pinfunction "2_2") (pintype "passive"))
      (node (ref "D4") (pin "2") (pinfunction "2_2") (pintype "passive"))
      (node (ref "D6") (pin "2") (pinfunction "2_2") (pintype "passive"))
      (node (ref "D7") (pin "2") (pinfunction "2_2") (pintype "passive"))
      (node (ref "D8") (pin "2") (pinfunction "2_2") (pintype "passive"))
      (node (ref "D9") (pin "1") (pinfunction "C_1") (pintype "passive"))
      (node (ref "DS1") (pin "2") (pinfunction "K_2") (pintype "passive"))
      (node (ref "J1") (pin "1") (pinfunction "1_1") (pintype "passive"))
      (node (ref "J1") (pin "MP1") (pinfunction "MP1_MP1") (pintype "passive"))
      (node (ref "J1") (pin "MP2") (pinfunction "MP2_MP2") (pintype "passive"))
      (node (ref "J10") (pin "1") (pinfunction "1_1") (pintype "passive"))
      (node (ref "J10") (pin "MP1") (pinfunction "MP1_MP1") (pintype "passive"))
      (node (ref "J10") (pin "MP2") (pinfunction "MP2_MP2") (pintype "passive"))
      (node (ref "J11") (pin "1") (pinfunction "1_1") (pintype "passive"))
      (node (ref "J11") (pin "MP1") (pinfunction "MP1_MP1") (pintype "passive"))
      (node (ref "J11") (pin "MP2") (pinfunction "MP2_MP2") (pintype "passive"))
      (node (ref "J12") (pin "4") (pinfunction "ID_4") (pintype "passive"))
      (node (ref "J12") (pin "5") (pinfunction "GND_5") (pintype "power_in"))
      (node (ref "J12") (pin "6") (pinfunction "SHLD1_6") (pintype "passive"))
      (node (ref "J12") (pin "7") (pinfunction "SHLD2_7") (pintype "passive"))
      (node (ref "J12") (pin "8") (pinfunction "SHLD3_8") (pintype "passive"))
      (node (ref "J12") (pin "9") (pinfunction "SHLD4_9") (pintype "passive"))
      (node (ref "J2") (pin "1") (pinfunction "1_1") (pintype "passive"))
      (node (ref "J2") (pin "MP1") (pinfunction "MP1_MP1") (pintype "passive"))
      (node (ref "J2") (pin "MP2") (pinfunction "MP2_MP2") (pintype "passive"))
      (node (ref "J3") (pin "4") (pinfunction "ID_4") (pintype "passive"))
      (node (ref "J3") (pin "5") (pinfunction "GND_5") (pintype "power_in"))
      (node (ref "J3") (pin "6") (pinfunction "SHLD1_6") (pintype "passive"))
      (node (ref "J3") (pin "7") (pinfunction "SHLD2_7") (pintype "passive"))
      (node (ref "J3") (pin "8") (pinfunction "SHLD3_8") (pintype "passive"))
      (node (ref "J3") (pin "9") (pinfunction "SHLD4_9") (pintype "passive"))
      (node (ref "J4") (pin "1") (pinfunction "1_1") (pintype "passive"))
      (node (ref "J4") (pin "MP1") (pinfunction "MP1_MP1") (pintype "passive"))
      (node (ref "J4") (pin "MP2") (pinfunction "MP2_MP2") (pintype "passive"))
      (node (ref "J5") (pin "1") (pinfunction "1_1") (pintype "passive"))
      (node (ref "J5") (pin "MP1") (pinfunction "MP1_MP1") (pintype "passive"))
      (node (ref "J5") (pin "MP2") (pinfunction "MP2_MP2") (pintype "passive"))
      (node (ref "J6") (pin "1") (pinfunction "1_1") (pintype "passive"))
      (node (ref "J6") (pin "MP1") (pinfunction "MP1_MP1") (pintype "passive"))
      (node (ref "J6") (pin "MP2") (pinfunction "MP2_MP2") (pintype "passive"))
      (node (ref "J7") (pin "1") (pinfunction "1_1") (pintype "passive"))
      (node (ref "J7") (pin "MP1") (pinfunction "MP1_MP1") (pintype "passive"))
      (node (ref "J7") (pin "MP2") (pinfunction "MP2_MP2") (pintype "passive"))
      (node (ref "J8") (pin "1") (pinfunction "1_1") (pintype "passive"))
      (node (ref "J8") (pin "MP1") (pinfunction "MP1_MP1") (pintype "passive"))
      (node (ref "J8") (pin "MP2") (pinfunction "MP2_MP2") (pintype "passive"))
      (node (ref "J9") (pin "1") (pinfunction "1_1") (pintype "passive"))
      (node (ref "J9") (pin "MP1") (pinfunction "MP1_MP1") (pintype "passive"))
      (node (ref "J9") (pin "MP2") (pinfunction "MP2_MP2") (pintype "passive"))
      (node (ref "LED1") (pin "1") (pinfunction "VSS_1") (pintype "passive"))
      (node (ref "R10") (pin "2") (pinfunction "2_2") (pintype "passive"))
      (node (ref "R7") (pin "2") (pinfunction "2_2") (pintype "passive"))
      (node (ref "S1") (pin "1") (pinfunction "NO_1_1") (pintype "passive"))
      (node (ref "S2") (pin "1") (pinfunction "NO_1_1") (pintype "passive"))
      (node (ref "U1") (pin "1") (pinfunction "GND_1_1") (pintype "passive"))
      (node (ref "U1") (pin "40") (pinfunction "GND_2_40") (pintype "passive"))
      (node (ref "U1") (pin "41") (pinfunction "GND_3_41") (pintype "passive"))
      (node (ref "U1") (pin "42") (pinfunction "GND_4_42") (pintype "passive"))
      (node (ref "U1") (pin "43") (pinfunction "GND_5_43") (pintype "passive"))
      (node (ref "U1") (pin "44") (pinfunction "GND_6_44") (pintype "passive"))
      (node (ref "U1") (pin "45") (pinfunction "GND_7_45") (pintype "passive"))
      (node (ref "U1") (pin "46") (pinfunction "GND_8_46") (pintype "passive"))
      (node (ref "U1") (pin "47") (pinfunction "GND_9_47") (pintype "passive"))
      (node (ref "U1") (pin "48") (pinfunction "GND_10_48") (pintype "passive"))
      (node (ref "U1") (pin "49") (pinfunction "GND_11_49") (pintype "passive"))
      (node (ref "U2") (pin "1") (pinfunction "GND_1") (pintype "passive"))
      (node (ref "U3") (pin "29") (pinfunction "GND_29") (pintype "power_in"))
      (node (ref "U3") (pin "3") (pinfunction "GND_3") (pintype "power_in"))
    )
    (net (code "43") (name "Net-(D9-A)") (class "Default")
      (node (ref "D9") (pin "2") (pinfunction "A_2") (pintype "passive"))
      (node (ref "R6") (pin "1") (pinfunction "1_1") (pintype "passive"))
    )
    (net (code "44") (name "Net-(Q1-B)") (class "Default")
      (node (ref "Q1") (pin "3") (pinfunction "B_3") (pintype "passive"))
      (node (ref "R5") (pin "1") (pinfunction "1_1") (pintype "passive"))
    )
    (net (code "45") (name "Net-(Q1-C)") (class "Default")
      (node (ref "Q1") (pin "1") (pinfunction "C_1") (pintype "passive"))
      (node (ref "R4") (pin "1") (pinfunction "1_1") (pintype "passive"))
    )
    (net (code "46") (name "Net-(Q2-B)") (class "Default")
      (node (ref "Q2") (pin "3") (pinfunction "B_3") (pintype "passive"))
      (node (ref "R8") (pin "1") (pinfunction "1_1") (pintype "passive"))
    )
    (net (code "47") (name "Net-(Q2-E)") (class "Default")
      (node (ref "Q2") (pin "2") (pinfunction "E_2") (pintype "passive"))
      (node (ref "R9") (pin "1") (pinfunction "1_1") (pintype "passive"))
    )
    (net (code "48") (name "Net-(U3-RXD)") (class "Default")
      (node (ref "R13") (pin "1") (pinfunction "1_1") (pintype "passive"))
      (node (ref "U3") (pin "25") (pinfunction "RXD_25") (pintype "input"))
    )
    (net (code "49") (name "Net-(U3-TXD)") (class "Default")
      (node (ref "R14") (pin "1") (pinfunction "1_1") (pintype "passive"))
      (node (ref "U3") (pin "26") (pinfunction "TXD_26") (pintype "output"))
    )
    (net (code "50") (name "Net-(U3-VBUS)") (class "Default")
      (node (ref "C6") (pin "1") (pinfunction "1_1") (pintype "passive"))
      (node (ref "R3") (pin "1") (pinfunction "1_1") (pintype "passive"))
      (node (ref "R7") (pin "1") (pinfunction "1_1") (pintype "passive"))
      (node (ref "U3") (pin "8") (pinfunction "VBUS_8") (pintype "input"))
    )
    (net (code "51") (name "Net-(U3-~{RST})") (class "Default")
      (node (ref "R11") (pin "2") (pinfunction "2_2") (pintype "passive"))
      (node (ref "U3") (pin "9") (pinfunction "~{RST}_9") (pintype "input"))
    )
    (net (code "52") (name "Net-(U3-~{SUSPEND})") (class "Default")
      (node (ref "R10") (pin "1") (pinfunction "1_1") (pintype "passive"))
      (node (ref "U3") (pin "11") (pinfunction "~{SUSPEND}_11") (pintype "output"))
    )
    (net (code "53") (name "VBUS") (class "Default")
      (node (ref "D1") (pin "2") (pinfunction "A_2") (pintype "passive"))
      (node (ref "D2") (pin "1") (pinfunction "1_1") (pintype "passive"))
      (node (ref "J3") (pin "1") (pinfunction "VBUS_1") (pintype "power_in"))
      (node (ref "R3") (pin "2") (pinfunction "2_2") (pintype "passive"))
    )
    (net (code "54") (name "VBUSB") (class "Default")
      (node (ref "D5") (pin "2") (pinfunction "A_2") (pintype "passive"))
      (node (ref "D6") (pin "1") (pinfunction "1_1") (pintype "passive"))
      (node (ref "J12") (pin "1") (pinfunction "VBUS_1") (pintype "power_in"))
    )
    (net (code "55") (name "VCC_3V3") (class "Default")
      (node (ref "C1") (pin "1") (pinfunction "1_1") (pintype "passive"))
      (node (ref "C10") (pin "1") (pinfunction "1_1") (pintype "passive"))
      (node (ref "C11") (pin "1") (pinfunction "1_1") (pintype "passive"))
      (node (ref "C2") (pin "1") (pinfunction "1_1") (pintype "passive"))
      (node (ref "C9") (pin "1") (pinfunction "1_1") (pintype "passive"))
      (node (ref "LED1") (pin "3") (pinfunction "VDD_3") (pintype "passive"))
      (node (ref "R1") (pin "1") (pinfunction "1_1") (pintype "passive"))
      (node (ref "R11") (pin "1") (pinfunction "1_1") (pintype "passive"))
      (node (ref "R6") (pin "2") (pinfunction "2_2") (pintype "passive"))
      (node (ref "U2") (pin "2") (pinfunction "VOUT_1_2") (pintype "passive"))
      (node (ref "U2") (pin "4") (pinfunction "VOUT_2_4") (pintype "passive"))
      (node (ref "U3") (pin "6") (pinfunction "VDD_6") (pintype "power_in"))
      (node (ref "U3") (pin "7") (pinfunction "VREGIN_7") (pintype "input"))
    )
    (net (code "56") (name "VCC_5V") (class "Default")
      (node (ref "C3") (pin "1") (pinfunction "1_1") (pintype "passive"))
      (node (ref "C4") (pin "1") (pinfunction "1_1") (pintype "passive"))
      (node (ref "C7") (pin "1") (pinfunction "1_1") (pintype "passive"))
      (node (ref "C8") (pin "1") (pinfunction "1_1") (pintype "passive"))
      (node (ref "D1") (pin "1") (pinfunction "C_1") (pintype "passive"))
      (node (ref "D5") (pin "1") (pinfunction "C_1") (pintype "passive"))
      (node (ref "U2") (pin "3") (pinfunction "VIN_3") (pintype "passive"))
    )
    (net (code "57") (name "unconnected-(LED1-DOUT-Pad4)") (class "Default")
      (node (ref "LED1") (pin "4") (pinfunction "DOUT_4") (pintype "passive+no_connect"))
    )
    (net (code "58") (name "unconnected-(S1-COM_1-Pad3)") (class "Default")
      (node (ref "S1") (pin "3") (pinfunction "COM_1_3") (pintype "passive+no_connect"))
    )
    (net (code "59") (name "unconnected-(S1-NO_2-Pad2)") (class "Default")
      (node (ref "S1") (pin "2") (pinfunction "NO_2_2") (pintype "passive+no_connect"))
    )
    (net (code "60") (name "unconnected-(S2-COM_1-Pad3)") (class "Default")
      (node (ref "S2") (pin "3") (pinfunction "COM_1_3") (pintype "passive+no_connect"))
    )
    (net (code "61") (name "unconnected-(S2-NO_2-Pad2)") (class "Default")
      (node (ref "S2") (pin "2") (pinfunction "NO_2_2") (pintype "passive+no_connect"))
    )
    (net (code "62") (name "unconnected-(U1-NC_1-Pad28)") (class "Default")
      (node (ref "U1") (pin "28") (pinfunction "NC_1_28") (pintype "passive+no_connect"))
    )
    (net (code "63") (name "unconnected-(U1-NC_2-Pad29)") (class "Default")
      (node (ref "U1") (pin "29") (pinfunction "NC_2_29") (pintype "passive+no_connect"))
    )
    (net (code "64") (name "unconnected-(U1-NC_3-Pad30)") (class "Default")
      (node (ref "U1") (pin "30") (pinfunction "NC_3_30") (pintype "passive+no_connect"))
    )
    (net (code "65") (name "unconnected-(U3-CHR0-Pad15)") (class "Default")
      (node (ref "U3") (pin "15") (pinfunction "CHR0_15") (pintype "output+no_connect"))
    )
    (net (code "66") (name "unconnected-(U3-CHR1-Pad14)") (class "Default")
      (node (ref "U3") (pin "14") (pinfunction "CHR1_14") (pintype "output+no_connect"))
    )
    (net (code "67") (name "unconnected-(U3-CHREN-Pad13)") (class "Default")
      (node (ref "U3") (pin "13") (pinfunction "CHREN_13") (pintype "output+no_connect"))
    )
    (net (code "68") (name "unconnected-(U3-CTS-Pad23)") (class "Default")
      (node (ref "U3") (pin "23") (pinfunction "CTS_23") (pintype "input+no_connect"))
    )
    (net (code "69") (name "unconnected-(U3-DCD-Pad1)") (class "Default")
      (node (ref "U3") (pin "1") (pinfunction "DCD_1") (pintype "input+no_connect"))
    )
    (net (code "70") (name "unconnected-(U3-DSR-Pad27)") (class "Default")
      (node (ref "U3") (pin "27") (pinfunction "DSR_27") (pintype "input+no_connect"))
    )
    (net (code "71") (name "unconnected-(U3-GPIO.0{slash}TXT-Pad19)") (class "Default")
      (node (ref "U3") (pin "19") (pinfunction "GPIO.0/TXT_19") (pintype "bidirectional+no_connect"))
    )
    (net (code "72") (name "unconnected-(U3-GPIO.1{slash}RXT-Pad18)") (class "Default")
      (node (ref "U3") (pin "18") (pinfunction "GPIO.1/RXT_18") (pintype "bidirectional+no_connect"))
    )
    (net (code "73") (name "unconnected-(U3-GPIO.2{slash}RS485-Pad17)") (class "Default")
      (node (ref "U3") (pin "17") (pinfunction "GPIO.2/RS485_17") (pintype "bidirectional+no_connect"))
    )
    (net (code "74") (name "unconnected-(U3-GPIO.3{slash}WAKEUP-Pad16)") (class "Default")
      (node (ref "U3") (pin "16") (pinfunction "GPIO.3/WAKEUP_16") (pintype "bidirectional+no_connect"))
    )
    (net (code "75") (name "unconnected-(U3-GPIO.4-Pad22)") (class "Default")
      (node (ref "U3") (pin "22") (pinfunction "GPIO.4_22") (pintype "bidirectional+no_connect"))
    )
    (net (code "76") (name "unconnected-(U3-GPIO.5-Pad21)") (class "Default")
      (node (ref "U3") (pin "21") (pinfunction "GPIO.5_21") (pintype "bidirectional+no_connect"))
    )
    (net (code "77") (name "unconnected-(U3-GPIO.6-Pad20)") (class "Default")
      (node (ref "U3") (pin "20") (pinfunction "GPIO.6_20") (pintype "bidirectional+no_connect"))
    )
    (net (code "78") (name "unconnected-(U3-NC-Pad10)") (class "Default")
      (node (ref "U3") (pin "10") (pinfunction "NC_10") (pintype "passive+no_connect"))
    )
    (net (code "79") (name "unconnected-(U3-SUSPEND-Pad12)") (class "Default")
      (node (ref "U3") (pin "12") (pinfunction "SUSPEND_12") (pintype "output+no_connect"))
    )
    (net (code "80") (name "unconnected-(U3-~{RI}{slash}CLK-Pad2)") (class "Default")
      (node (ref "U3") (pin "2") (pinfunction "~{RI}/CLK_2") (pintype "bidirectional+no_connect"))
    )
  )
)
